# Seven-Seg_Displays.net
KiCad netlist of a schematic drawn in Altium Designer
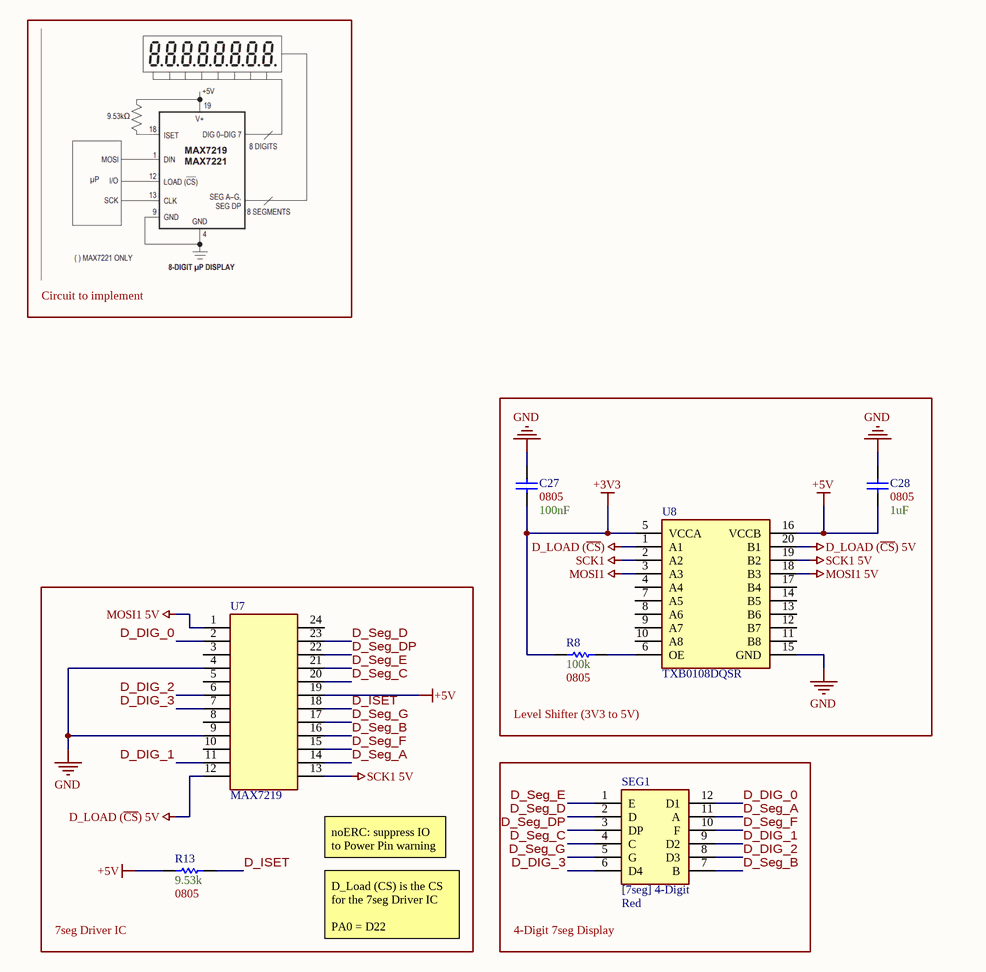
[diagram p0: Seven-Seg Displays.SchDoc]

(export (version "E")
  (design (tool "Eeschema 10.0.6"))
  (components
    (comp (ref "C27")
      (value "[Cap] SMD Nonpolarized")
      (footprint "[Cap] SMD 0805")
      (fields (field (name "SIZE PACKAGE") "0805") (field (name "CAPACITANCE") "100nF"))
      (libsource (lib "RADM Components") (part "[Cap] SMD Nonpolarized"))
    )
    (comp (ref "C28")
      (value "[Cap] SMD Nonpolarized")
      (footprint "[Cap] SMD 0805")
      (fields (field (name "SIZE PACKAGE") "0805") (field (name "CAPACITANCE") "1uF"))
      (libsource (lib "RADM Components") (part "[Cap] SMD Nonpolarized"))
    )
    (comp (ref "R8")
      (value "[Res] SMD Resistor")
      (footprint "[Res] SMD 0805")
      (fields (field (name "RESISTANCE") "100k") (field (name "SIZE PACKAGE") "0805"))
      (libsource (lib "RADM Components") (part "[Res] SMD Resistor"))
    )
    (comp (ref "R13")
      (value "[Res] SMD Resistor")
      (footprint "[Res] SMD 0805")
      (fields (field (name "RESISTANCE") "9.53k") (field (name "SIZE PACKAGE") "0805"))
      (libsource (lib "RADM Components") (part "[Res] SMD Resistor"))
    )
    (comp (ref "SEG1")
      (value "[7seg] 4-Digit")
      (footprint "[7seg] 4-Digit")
      (fields (field (name "MOUSER PART #") "474-COM-11405") (field (name "COLOR") "Red"))
      (libsource (lib "RADM Components") (part "[7seg] 4-Digit"))
    )
    (comp (ref "U7")
      (value "MAX7219")
      (footprint "[DIP IC] 24pin, Socket")
      (libsource (lib "RADM Components") (part "[DIP IC] 24pin"))
    )
    (comp (ref "U8")
      (value "TXB0108DQSR")
      (footprint "[IC] Level Shifter")
      (libsource (lib "RADM Components") (part "[IC] Level Shifter"))
    )
  )
  (nets
    (net (code "1") (name "+3V3") (class "Default")
      (node (ref "C27") (pin "1") (pinfunction "1_1") (pintype "passive"))
      (node (ref "R8") (pin "1") (pinfunction "1_1") (pintype "passive"))
      (node (ref "U8") (pin "5") (pinfunction "VCCA_5") (pintype "passive"))
    )
    (net (code "2") (name "+5V") (class "Default")
      (node (ref "C28") (pin "1") (pinfunction "1_1") (pintype "passive"))
      (node (ref "R13") (pin "1") (pinfunction "1_1") (pintype "passive"))
      (node (ref "U7") (pin "19") (pintype "power_in"))
      (node (ref "U8") (pin "16") (pinfunction "VCCB_16") (pintype "passive"))
    )
    (net (code "3") (name "/D_DIG_0") (class "Default")
      (node (ref "SEG1") (pin "12") (pinfunction "D1_12") (pintype "power_in"))
      (node (ref "U7") (pin "2") (pintype "power_in"))
    )
    (net (code "4") (name "/D_DIG_1") (class "Default")
      (node (ref "SEG1") (pin "9") (pinfunction "D2_9") (pintype "power_in"))
      (node (ref "U7") (pin "11") (pintype "power_in"))
    )
    (net (code "5") (name "/D_DIG_2") (class "Default")
      (node (ref "SEG1") (pin "8") (pinfunction "D3_8") (pintype "power_in"))
      (node (ref "U7") (pin "6") (pintype "power_in"))
    )
    (net (code "6") (name "/D_DIG_3") (class "Default")
      (node (ref "SEG1") (pin "6") (pinfunction "D4_6") (pintype "power_in"))
      (node (ref "U7") (pin "7") (pintype "power_in"))
    )
    (net (code "7") (name "/D_ISET") (class "Default")
      (node (ref "R13") (pin "2") (pinfunction "2_2") (pintype "passive"))
      (node (ref "U7") (pin "18") (pintype "power_in"))
    )
    (net (code "8") (name "/D_Seg_A") (class "Default")
      (node (ref "SEG1") (pin "11") (pinfunction "A_11") (pintype "power_in"))
      (node (ref "U7") (pin "14") (pintype "power_in"))
    )
    (net (code "9") (name "/D_Seg_B") (class "Default")
      (node (ref "SEG1") (pin "7") (pinfunction "B_7") (pintype "power_in"))
      (node (ref "U7") (pin "16") (pintype "power_in"))
    )
    (net (code "10") (name "/D_Seg_C") (class "Default")
      (node (ref "SEG1") (pin "4") (pinfunction "C_4") (pintype "power_in"))
      (node (ref "U7") (pin "20") (pintype "power_in"))
    )
    (net (code "11") (name "/D_Seg_D") (class "Default")
      (node (ref "SEG1") (pin "2") (pinfunction "D_2") (pintype "power_in"))
      (node (ref "U7") (pin "23") (pintype "power_in"))
    )
    (net (code "12") (name "/D_Seg_DP") (class "Default")
      (node (ref "SEG1") (pin "3") (pinfunction "DP_3") (pintype "power_in"))
      (node (ref "U7") (pin "22") (pintype "power_in"))
    )
    (net (code "13") (name "/D_Seg_E") (class "Default")
      (node (ref "SEG1") (pin "1") (pinfunction "E_1") (pintype "power_in"))
      (node (ref "U7") (pin "21") (pintype "power_in"))
    )
    (net (code "14") (name "/D_Seg_F") (class "Default")
      (node (ref "SEG1") (pin "10") (pinfunction "F_10") (pintype "power_in"))
      (node (ref "U7") (pin "15") (pintype "power_in"))
    )
    (net (code "15") (name "/D_Seg_G") (class "Default")
      (node (ref "SEG1") (pin "5") (pinfunction "G_5") (pintype "power_in"))
      (node (ref "U7") (pin "17") (pintype "power_in"))
    )
    (net (code "16") (name "D_LOAD (~{CS})") (class "Default")
      (node (ref "U8") (pin "1") (pinfunction "A1_1") (pintype "passive"))
    )
    (net (code "17") (name "D_LOAD (~{CS}) 5V") (class "Default")
      (node (ref "U7") (pin "12") (pintype "power_in"))
      (node (ref "U8") (pin "20") (pinfunction "B1_20") (pintype "passive"))
    )
    (net (code "18") (name "GND") (class "Default")
      (node (ref "C27") (pin "2") (pinfunction "2_2") (pintype "passive"))
      (node (ref "C28") (pin "2") (pinfunction "2_2") (pintype "passive"))
      (node (ref "U7") (pin "4") (pintype "power_in"))
      (node (ref "U7") (pin "9") (pintype "power_in"))
      (node (ref "U8") (pin "15") (pinfunction "GND_15") (pintype "passive"))
    )
    (net (code "19") (name "MOSI1") (class "Default")
      (node (ref "U8") (pin "3") (pinfunction "A3_3") (pintype "passive"))
    )
    (net (code "20") (name "MOSI1 5V") (class "Default")
      (node (ref "U7") (pin "1") (pintype "power_in"))
      (node (ref "U8") (pin "18") (pinfunction "B3_18") (pintype "passive"))
    )
    (net (code "21") (name "Net-(U8-OE)") (class "Default")
      (node (ref "R8") (pin "2") (pinfunction "2_2") (pintype "passive"))
      (node (ref "U8") (pin "6") (pinfunction "OE_6") (pintype "passive"))
    )
    (net (code "22") (name "SCK1") (class "Default")
      (node (ref "U8") (pin "2") (pinfunction "A2_2") (pintype "passive"))
    )
    (net (code "23") (name "SCK1 5V") (class "Default")
      (node (ref "U7") (pin "13") (pintype "power_in"))
      (node (ref "U8") (pin "19") (pinfunction "B2_19") (pintype "passive"))
    )
    (net (code "24") (name "unconnected-(U7-Pad3)") (class "Default")
      (node (ref "U7") (pin "3") (pintype "power_in"))
    )
    (net (code "25") (name "unconnected-(U7-Pad5)") (class "Default")
      (node (ref "U7") (pin "5") (pintype "power_in"))
    )
    (net (code "26") (name "unconnected-(U7-Pad8)") (class "Default")
      (node (ref "U7") (pin "8") (pintype "power_in"))
    )
    (net (code "27") (name "unconnected-(U7-Pad10)") (class "Default")
      (node (ref "U7") (pin "10") (pintype "power_in"))
    )
    (net (code "28") (name "unconnected-(U7-Pad24)") (class "Default")
      (node (ref "U7") (pin "24") (pintype "power_in"))
    )
    (net (code "29") (name "unconnected-(U8-A4-Pad4)") (class "Default")
      (node (ref "U8") (pin "4") (pinfunction "A4_4") (pintype "passive"))
    )
    (net (code "30") (name "unconnected-(U8-A5-Pad7)") (class "Default")
      (node (ref "U8") (pin "7") (pinfunction "A5_7") (pintype "passive"))
    )
    (net (code "31") (name "unconnected-(U8-A6-Pad8)") (class "Default")
      (node (ref "U8") (pin "8") (pinfunction "A6_8") (pintype "passive"))
    )
    (net (code "32") (name "unconnected-(U8-A7-Pad9)") (class "Default")
      (node (ref "U8") (pin "9") (pinfunction "A7_9") (pintype "passive"))
    )
    (net (code "33") (name "unconnected-(U8-A8-Pad10)") (class "Default")
      (node (ref "U8") (pin "10") (pinfunction "A8_10") (pintype "passive"))
    )
    (net (code "34") (name "unconnected-(U8-B4-Pad17)") (class "Default")
      (node (ref "U8") (pin "17") (pinfunction "B4_17") (pintype "passive"))
    )
    (net (code "35") (name "unconnected-(U8-B5-Pad14)") (class "Default")
      (node (ref "U8") (pin "14") (pinfunction "B5_14") (pintype "passive"))
    )
    (net (code "36") (name "unconnected-(U8-B6-Pad13)") (class "Default")
      (node (ref "U8") (pin "13") (pinfunction "B6_13") (pintype "passive"))
    )
    (net (code "37") (name "unconnected-(U8-B7-Pad12)") (class "Default")
      (node (ref "U8") (pin "12") (pinfunction "B7_12") (pintype "passive"))
    )
    (net (code "38") (name "unconnected-(U8-B8-Pad11)") (class "Default")
      (node (ref "U8") (pin "11") (pinfunction "B8_11") (pintype "passive"))
    )
  )
)
